# chipchestra-v05.net
KiCad netlist of a schematic drawn in EAGLE
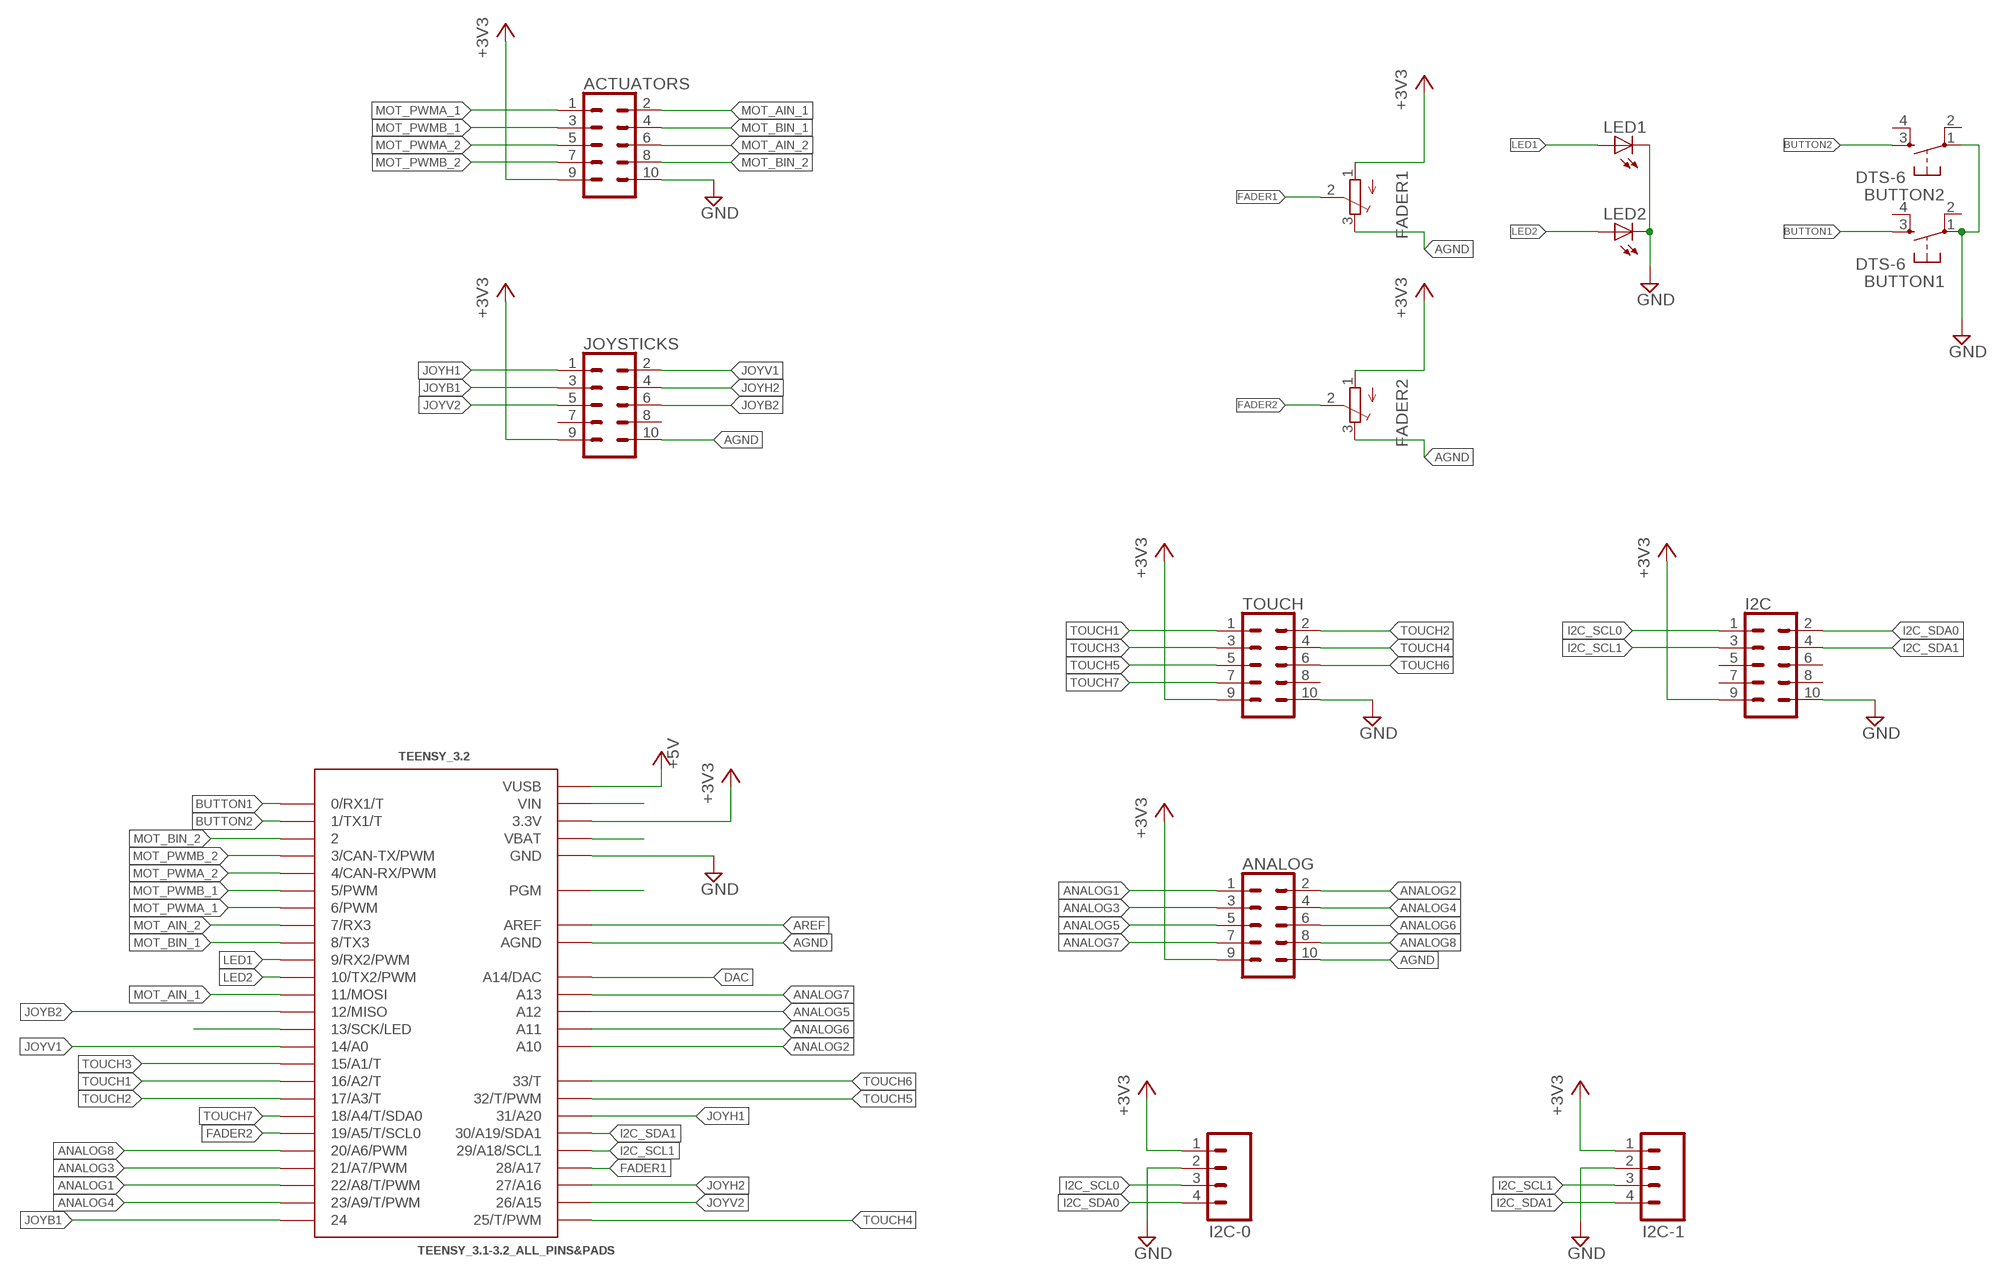
[diagram p0: schematic, sheet 1]

(export (version "E")
  (design (tool "Eeschema 10.0.6"))
  (components
    (comp (ref "ACTUATORS")
      (value "CONN_05X2SHD_LOCK")
      (footprint "eagle-import:2X5-SHROUDED_LOCK")
      (libsource (lib "eagle-import") (part "CONN_05X2SHD_LOCK"))
    )
    (comp (ref "ANALOG")
      (value "CONN_05X2SHD_LOCK")
      (footprint "eagle-import:2X5-SHROUDED_LOCK")
      (libsource (lib "eagle-import") (part "CONN_05X2SHD_LOCK"))
    )
    (comp (ref "BUTTON1")
      (value "DTS-6")
      (footprint "eagle-import:DTS-6")
      (libsource (lib "eagle-import") (part "DTS-6"))
    )
    (comp (ref "BUTTON2")
      (value "DTS-6")
      (footprint "eagle-import:DTS-6")
      (libsource (lib "eagle-import") (part "DTS-6"))
    )
    (comp (ref "FADER1")
      (value "TRIMPOT3386")
      (footprint "eagle-import:TRIM-3386")
      (libsource (lib "eagle-import") (part "TRIMPOT3386"))
    )
    (comp (ref "FADER2")
      (value "TRIMPOT3386")
      (footprint "eagle-import:TRIM-3386")
      (libsource (lib "eagle-import") (part "TRIMPOT3386"))
    )
    (comp (ref "I2C")
      (value "CONN_05X2SHD_LOCK")
      (footprint "eagle-import:2X5-SHROUDED_LOCK")
      (libsource (lib "eagle-import") (part "CONN_05X2SHD_LOCK"))
    )
    (comp (ref "I2C-0")
      (value "M04LOCK")
      (footprint "eagle-import:1X04_LOCK")
      (libsource (lib "eagle-import") (part "M04LOCK"))
    )
    (comp (ref "I2C-1")
      (value "M04LOCK")
      (footprint "eagle-import:1X04_LOCK")
      (libsource (lib "eagle-import") (part "M04LOCK"))
    )
    (comp (ref "JOYSTICKS")
      (value "CONN_05X2SHD_LOCK")
      (footprint "eagle-import:2X5-SHROUDED_LOCK")
      (libsource (lib "eagle-import") (part "CONN_05X2SHD_LOCK"))
    )
    (comp (ref "LED1")
      (value "LED3MM")
      (footprint "eagle-import:LED3MM")
      (libsource (lib "eagle-import") (part "LED3MM"))
    )
    (comp (ref "LED2")
      (value "LED3MM")
      (footprint "eagle-import:LED3MM")
      (libsource (lib "eagle-import") (part "LED3MM"))
    )
    (comp (ref "TEENSY_3.2")
      (value "TEENSY_3.1-3.2_ALL_PINS&PADS")
      (footprint "eagle-import:TEENSY_3.0-3.2_ALL_PINS_&_PADS")
      (libsource (lib "eagle-import") (part "TEENSY_3.1-3.2_ALL_PINS&PADS"))
    )
    (comp (ref "TOUCH")
      (value "CONN_05X2SHD_LOCK")
      (footprint "eagle-import:2X5-SHROUDED_LOCK")
      (libsource (lib "eagle-import") (part "CONN_05X2SHD_LOCK"))
    )
  )
  (nets
    (net (code "1") (name "+3V3") (class "Default")
      (node (ref "ACTUATORS") (pin "9") (pinfunction "9_9") (pintype "passive"))
      (node (ref "ANALOG") (pin "9") (pinfunction "9_9") (pintype "passive"))
      (node (ref "FADER1") (pin "1") (pinfunction "A_1") (pintype "passive"))
      (node (ref "FADER2") (pin "1") (pinfunction "A_1") (pintype "passive"))
      (node (ref "I2C") (pin "9") (pinfunction "9_9") (pintype "passive"))
      (node (ref "I2C-0") (pin "1") (pinfunction "1_1") (pintype "passive"))
      (node (ref "I2C-1") (pin "1") (pinfunction "1_1") (pintype "passive"))
      (node (ref "JOYSTICKS") (pin "9") (pinfunction "9_9") (pintype "passive"))
      (node (ref "TEENSY_3.2") (pin "3.3V") (pinfunction "3.3V_3.3V") (pintype "power_in"))
      (node (ref "TEENSY_3.2") (pin "3.3V1") (pinfunction "3.3V_3.3V1") (pintype "power_in"))
      (node (ref "TEENSY_3.2") (pin "3.3V2") (pinfunction "3.3V_3.3V2") (pintype "power_in"))
      (node (ref "TOUCH") (pin "9") (pinfunction "9_9") (pintype "passive"))
    )
    (net (code "2") (name "+5V") (class "Default")
      (node (ref "TEENSY_3.2") (pin "VUSB") (pinfunction "VUSB_VUSB") (pintype "power_in"))
    )
    (net (code "3") (name "AGND") (class "Default")
      (node (ref "ANALOG") (pin "10") (pinfunction "10_10") (pintype "passive"))
      (node (ref "FADER1") (pin "3") (pinfunction "E_3") (pintype "passive"))
      (node (ref "FADER2") (pin "3") (pinfunction "E_3") (pintype "passive"))
      (node (ref "JOYSTICKS") (pin "10") (pinfunction "10_10") (pintype "passive"))
      (node (ref "TEENSY_3.2") (pin "AGND") (pinfunction "AGND_AGND") (pintype "power_in"))
    )
    (net (code "4") (name "ANALOG1") (class "Default")
      (node (ref "ANALOG") (pin "1") (pinfunction "1_1") (pintype "passive"))
      (node (ref "TEENSY_3.2") (pin "22/A8") (pinfunction "22/A8/T/PWM_22/A8") (pintype "bidirectional"))
    )
    (net (code "5") (name "ANALOG2") (class "Default")
      (node (ref "ANALOG") (pin "2") (pinfunction "2_2") (pintype "passive"))
      (node (ref "TEENSY_3.2") (pin "A10") (pinfunction "A10_A10") (pintype "bidirectional"))
    )
    (net (code "6") (name "ANALOG3") (class "Default")
      (node (ref "ANALOG") (pin "3") (pinfunction "3_3") (pintype "passive"))
      (node (ref "TEENSY_3.2") (pin "21/A7") (pinfunction "21/A7/PWM_21/A7") (pintype "bidirectional"))
    )
    (net (code "7") (name "ANALOG4") (class "Default")
      (node (ref "ANALOG") (pin "4") (pinfunction "4_4") (pintype "passive"))
      (node (ref "TEENSY_3.2") (pin "23/A9") (pinfunction "23/A9/T/PWM_23/A9") (pintype "bidirectional"))
    )
    (net (code "8") (name "ANALOG5") (class "Default")
      (node (ref "ANALOG") (pin "5") (pinfunction "5_5") (pintype "passive"))
      (node (ref "TEENSY_3.2") (pin "A12") (pinfunction "A12_A12") (pintype "bidirectional"))
    )
    (net (code "9") (name "ANALOG6") (class "Default")
      (node (ref "ANALOG") (pin "6") (pinfunction "6_6") (pintype "passive"))
      (node (ref "TEENSY_3.2") (pin "A11") (pinfunction "A11_A11") (pintype "bidirectional"))
    )
    (net (code "10") (name "ANALOG7") (class "Default")
      (node (ref "ANALOG") (pin "7") (pinfunction "7_7") (pintype "passive"))
      (node (ref "TEENSY_3.2") (pin "A13") (pinfunction "A13_A13") (pintype "bidirectional"))
    )
    (net (code "11") (name "ANALOG8") (class "Default")
      (node (ref "ANALOG") (pin "8") (pinfunction "8_8") (pintype "passive"))
      (node (ref "TEENSY_3.2") (pin "20/A6") (pinfunction "20/A6/PWM_20/A6") (pintype "bidirectional"))
    )
    (net (code "12") (name "AREF") (class "Default")
      (node (ref "TEENSY_3.2") (pin "AREF") (pinfunction "AREF_AREF") (pintype "power_in"))
    )
    (net (code "13") (name "BUTTON1") (class "Default")
      (node (ref "BUTTON1") (pin "3") (pinfunction "3_3") (pintype "passive"))
      (node (ref "TEENSY_3.2") (pin "0") (pinfunction "0/RX1/T_0") (pintype "bidirectional"))
    )
    (net (code "14") (name "BUTTON2") (class "Default")
      (node (ref "BUTTON2") (pin "3") (pinfunction "3_3") (pintype "passive"))
      (node (ref "TEENSY_3.2") (pin "1") (pinfunction "1/TX1/T_1") (pintype "bidirectional"))
    )
    (net (code "15") (name "DAC") (class "Default")
      (node (ref "TEENSY_3.2") (pin "RESET/DAC") (pinfunction "A14/DAC_RESET/DAC") (pintype "bidirectional"))
    )
    (net (code "16") (name "FADER1") (class "Default")
      (node (ref "FADER1") (pin "2") (pinfunction "S_2") (pintype "passive"))
      (node (ref "TEENSY_3.2") (pin "28") (pinfunction "28/A17_28") (pintype "bidirectional"))
    )
    (net (code "17") (name "FADER2") (class "Default")
      (node (ref "FADER2") (pin "2") (pinfunction "S_2") (pintype "passive"))
      (node (ref "TEENSY_3.2") (pin "19/A5") (pinfunction "19/A5/T/SCL0_19/A5") (pintype "bidirectional"))
    )
    (net (code "18") (name "GND") (class "Default")
      (node (ref "ACTUATORS") (pin "10") (pinfunction "10_10") (pintype "passive"))
      (node (ref "BUTTON1") (pin "1") (pinfunction "1_1") (pintype "passive"))
      (node (ref "BUTTON2") (pin "1") (pinfunction "1_1") (pintype "passive"))
      (node (ref "I2C") (pin "10") (pinfunction "10_10") (pintype "passive"))
      (node (ref "I2C-0") (pin "2") (pinfunction "2_2") (pintype "passive"))
      (node (ref "I2C-1") (pin "2") (pinfunction "2_2") (pintype "passive"))
      (node (ref "LED1") (pin "K") (pinfunction "C_K") (pintype "passive"))
      (node (ref "LED2") (pin "K") (pinfunction "C_K") (pintype "passive"))
      (node (ref "TEENSY_3.2") (pin "GND") (pinfunction "GND_GND") (pintype "power_in"))
      (node (ref "TEENSY_3.2") (pin "GND1") (pinfunction "GND_GND1") (pintype "power_in"))
      (node (ref "TEENSY_3.2") (pin "GND2") (pinfunction "GND_GND2") (pintype "power_in"))
      (node (ref "TOUCH") (pin "10") (pinfunction "10_10") (pintype "passive"))
    )
    (net (code "19") (name "I2C_SCL0") (class "Default")
      (node (ref "I2C") (pin "1") (pinfunction "1_1") (pintype "passive"))
      (node (ref "I2C-0") (pin "3") (pinfunction "3_3") (pintype "passive"))
    )
    (net (code "20") (name "I2C_SCL1") (class "Default")
      (node (ref "I2C") (pin "3") (pinfunction "3_3") (pintype "passive"))
      (node (ref "I2C-1") (pin "3") (pinfunction "3_3") (pintype "passive"))
      (node (ref "TEENSY_3.2") (pin "29") (pinfunction "29/A18/SCL1_29") (pintype "bidirectional"))
    )
    (net (code "21") (name "I2C_SDA0") (class "Default")
      (node (ref "I2C") (pin "2") (pinfunction "2_2") (pintype "passive"))
      (node (ref "I2C-0") (pin "4") (pinfunction "4_4") (pintype "passive"))
    )
    (net (code "22") (name "I2C_SDA1") (class "Default")
      (node (ref "I2C") (pin "4") (pinfunction "4_4") (pintype "passive"))
      (node (ref "I2C-1") (pin "4") (pinfunction "4_4") (pintype "passive"))
      (node (ref "TEENSY_3.2") (pin "30") (pinfunction "30/A19/SDA1_30") (pintype "bidirectional"))
    )
    (net (code "23") (name "JOYB1") (class "Default")
      (node (ref "JOYSTICKS") (pin "3") (pinfunction "3_3") (pintype "passive"))
      (node (ref "TEENSY_3.2") (pin "24") (pinfunction "24_24") (pintype "bidirectional"))
    )
    (net (code "24") (name "JOYB2") (class "Default")
      (node (ref "JOYSTICKS") (pin "6") (pinfunction "6_6") (pintype "passive"))
      (node (ref "TEENSY_3.2") (pin "12") (pinfunction "12/MISO_12") (pintype "bidirectional"))
    )
    (net (code "25") (name "JOYH1") (class "Default")
      (node (ref "JOYSTICKS") (pin "1") (pinfunction "1_1") (pintype "passive"))
      (node (ref "TEENSY_3.2") (pin "31") (pinfunction "31/A20_31") (pintype "bidirectional"))
    )
    (net (code "26") (name "JOYH2") (class "Default")
      (node (ref "JOYSTICKS") (pin "4") (pinfunction "4_4") (pintype "passive"))
      (node (ref "TEENSY_3.2") (pin "27") (pinfunction "27/A16_27") (pintype "bidirectional"))
    )
    (net (code "27") (name "JOYV1") (class "Default")
      (node (ref "JOYSTICKS") (pin "2") (pinfunction "2_2") (pintype "passive"))
      (node (ref "TEENSY_3.2") (pin "14/A0") (pinfunction "14/A0_14/A0") (pintype "bidirectional"))
    )
    (net (code "28") (name "JOYV2") (class "Default")
      (node (ref "JOYSTICKS") (pin "5") (pinfunction "5_5") (pintype "passive"))
      (node (ref "TEENSY_3.2") (pin "26") (pinfunction "26/A15_26") (pintype "bidirectional"))
    )
    (net (code "29") (name "LED1") (class "Default")
      (node (ref "LED1") (pin "A") (pinfunction "A_A") (pintype "passive"))
      (node (ref "TEENSY_3.2") (pin "9") (pinfunction "9/RX2/PWM_9") (pintype "bidirectional"))
    )
    (net (code "30") (name "LED2") (class "Default")
      (node (ref "LED2") (pin "A") (pinfunction "A_A") (pintype "passive"))
      (node (ref "TEENSY_3.2") (pin "10") (pinfunction "10/TX2/PWM_10") (pintype "bidirectional"))
    )
    (net (code "31") (name "MOT_AIN_1") (class "Default")
      (node (ref "ACTUATORS") (pin "2") (pinfunction "2_2") (pintype "passive"))
      (node (ref "TEENSY_3.2") (pin "11") (pinfunction "11/MOSI_11") (pintype "bidirectional"))
    )
    (net (code "32") (name "MOT_AIN_2") (class "Default")
      (node (ref "ACTUATORS") (pin "6") (pinfunction "6_6") (pintype "passive"))
      (node (ref "TEENSY_3.2") (pin "7") (pinfunction "7/RX3_7") (pintype "bidirectional"))
    )
    (net (code "33") (name "MOT_BIN_1") (class "Default")
      (node (ref "ACTUATORS") (pin "4") (pinfunction "4_4") (pintype "passive"))
      (node (ref "TEENSY_3.2") (pin "8") (pinfunction "8/TX3_8") (pintype "bidirectional"))
    )
    (net (code "34") (name "MOT_BIN_2") (class "Default")
      (node (ref "ACTUATORS") (pin "8") (pinfunction "8_8") (pintype "passive"))
      (node (ref "TEENSY_3.2") (pin "2") (pinfunction "2_2") (pintype "bidirectional"))
    )
    (net (code "35") (name "MOT_PWMA_1") (class "Default")
      (node (ref "ACTUATORS") (pin "1") (pinfunction "1_1") (pintype "passive"))
      (node (ref "TEENSY_3.2") (pin "6") (pinfunction "6/PWM_6") (pintype "bidirectional"))
    )
    (net (code "36") (name "MOT_PWMA_2") (class "Default")
      (node (ref "ACTUATORS") (pin "5") (pinfunction "5_5") (pintype "passive"))
      (node (ref "TEENSY_3.2") (pin "4") (pinfunction "4/CAN-RX/PWM_4") (pintype "bidirectional"))
    )
    (net (code "37") (name "MOT_PWMB_1") (class "Default")
      (node (ref "ACTUATORS") (pin "3") (pinfunction "3_3") (pintype "passive"))
      (node (ref "TEENSY_3.2") (pin "5") (pinfunction "5/PWM_5") (pintype "bidirectional"))
    )
    (net (code "38") (name "MOT_PWMB_2") (class "Default")
      (node (ref "ACTUATORS") (pin "7") (pinfunction "7_7") (pintype "passive"))
      (node (ref "TEENSY_3.2") (pin "3") (pinfunction "3/CAN-TX/PWM_3") (pintype "bidirectional"))
    )
    (net (code "39") (name "TOUCH1") (class "Default")
      (node (ref "TEENSY_3.2") (pin "16/A2") (pinfunction "16/A2/T_16/A2") (pintype "bidirectional"))
      (node (ref "TOUCH") (pin "1") (pinfunction "1_1") (pintype "passive"))
    )
    (net (code "40") (name "TOUCH2") (class "Default")
      (node (ref "TEENSY_3.2") (pin "17/A3") (pinfunction "17/A3/T_17/A3") (pintype "bidirectional"))
      (node (ref "TOUCH") (pin "2") (pinfunction "2_2") (pintype "passive"))
    )
    (net (code "41") (name "TOUCH3") (class "Default")
      (node (ref "TEENSY_3.2") (pin "15/A1") (pinfunction "15/A1/T_15/A1") (pintype "bidirectional"))
      (node (ref "TOUCH") (pin "3") (pinfunction "3_3") (pintype "passive"))
    )
    (net (code "42") (name "TOUCH4") (class "Default")
      (node (ref "TEENSY_3.2") (pin "25") (pinfunction "25/T/PWM_25") (pintype "bidirectional"))
      (node (ref "TOUCH") (pin "4") (pinfunction "4_4") (pintype "passive"))
    )
    (net (code "43") (name "TOUCH5") (class "Default")
      (node (ref "TEENSY_3.2") (pin "32") (pinfunction "32/T/PWM_32") (pintype "bidirectional"))
      (node (ref "TOUCH") (pin "5") (pinfunction "5_5") (pintype "passive"))
    )
    (net (code "44") (name "TOUCH6") (class "Default")
      (node (ref "TEENSY_3.2") (pin "33") (pinfunction "33/T_33") (pintype "bidirectional"))
      (node (ref "TOUCH") (pin "6") (pinfunction "6_6") (pintype "passive"))
    )
    (net (code "45") (name "TOUCH7") (class "Default")
      (node (ref "TEENSY_3.2") (pin "18/A4") (pinfunction "18/A4/T/SDA0_18/A4") (pintype "bidirectional"))
      (node (ref "TOUCH") (pin "7") (pinfunction "7_7") (pintype "passive"))
    )
    (net (code "46") (name "unconnected-(BUTTON1-Pad2)") (class "Default")
      (node (ref "BUTTON1") (pin "2") (pinfunction "2_2") (pintype "passive"))
    )
    (net (code "47") (name "unconnected-(BUTTON1-Pad4)") (class "Default")
      (node (ref "BUTTON1") (pin "4") (pinfunction "4_4") (pintype "passive"))
    )
    (net (code "48") (name "unconnected-(BUTTON2-Pad2)") (class "Default")
      (node (ref "BUTTON2") (pin "2") (pinfunction "2_2") (pintype "passive"))
    )
    (net (code "49") (name "unconnected-(BUTTON2-Pad4)") (class "Default")
      (node (ref "BUTTON2") (pin "4") (pinfunction "4_4") (pintype "passive"))
    )
    (net (code "50") (name "unconnected-(I2C-Pad5)") (class "Default")
      (node (ref "I2C") (pin "5") (pinfunction "5_5") (pintype "passive"))
    )
    (net (code "51") (name "unconnected-(I2C-Pad6)") (class "Default")
      (node (ref "I2C") (pin "6") (pinfunction "6_6") (pintype "passive"))
    )
    (net (code "52") (name "unconnected-(I2C-Pad7)") (class "Default")
      (node (ref "I2C") (pin "7") (pinfunction "7_7") (pintype "passive"))
    )
    (net (code "53") (name "unconnected-(I2C-Pad8)") (class "Default")
      (node (ref "I2C") (pin "8") (pinfunction "8_8") (pintype "passive"))
    )
    (net (code "54") (name "unconnected-(JOYSTICKS-Pad7)") (class "Default")
      (node (ref "JOYSTICKS") (pin "7") (pinfunction "7_7") (pintype "passive"))
    )
    (net (code "55") (name "unconnected-(JOYSTICKS-Pad8)") (class "Default")
      (node (ref "JOYSTICKS") (pin "8") (pinfunction "8_8") (pintype "passive"))
    )
    (net (code "56") (name "unconnected-(TEENSY_3.2-13{slash}SCK{slash}LED-Pad13)") (class "Default")
      (node (ref "TEENSY_3.2") (pin "13") (pinfunction "13/SCK/LED_13") (pintype "bidirectional"))
    )
    (net (code "57") (name "unconnected-(TEENSY_3.2-PadPGM)") (class "Default")
      (node (ref "TEENSY_3.2") (pin "PGM") (pinfunction "PGM_PGM") (pintype "bidirectional"))
    )
    (net (code "58") (name "unconnected-(TEENSY_3.2-PadVBAT)") (class "Default")
      (node (ref "TEENSY_3.2") (pin "VBAT") (pinfunction "VBAT_VBAT") (pintype "power_in"))
    )
    (net (code "59") (name "unconnected-(TEENSY_3.2-PadVIN)") (class "Default")
      (node (ref "TEENSY_3.2") (pin "VIN") (pinfunction "VIN_VIN") (pintype "power_in"))
    )
    (net (code "60") (name "unconnected-(TOUCH-Pad8)") (class "Default")
      (node (ref "TOUCH") (pin "8") (pinfunction "8_8") (pintype "passive"))
    )
  )
)
